# NvideaJetsonUSB.net
KiCad netlist of a schematic drawn in Altium Designer
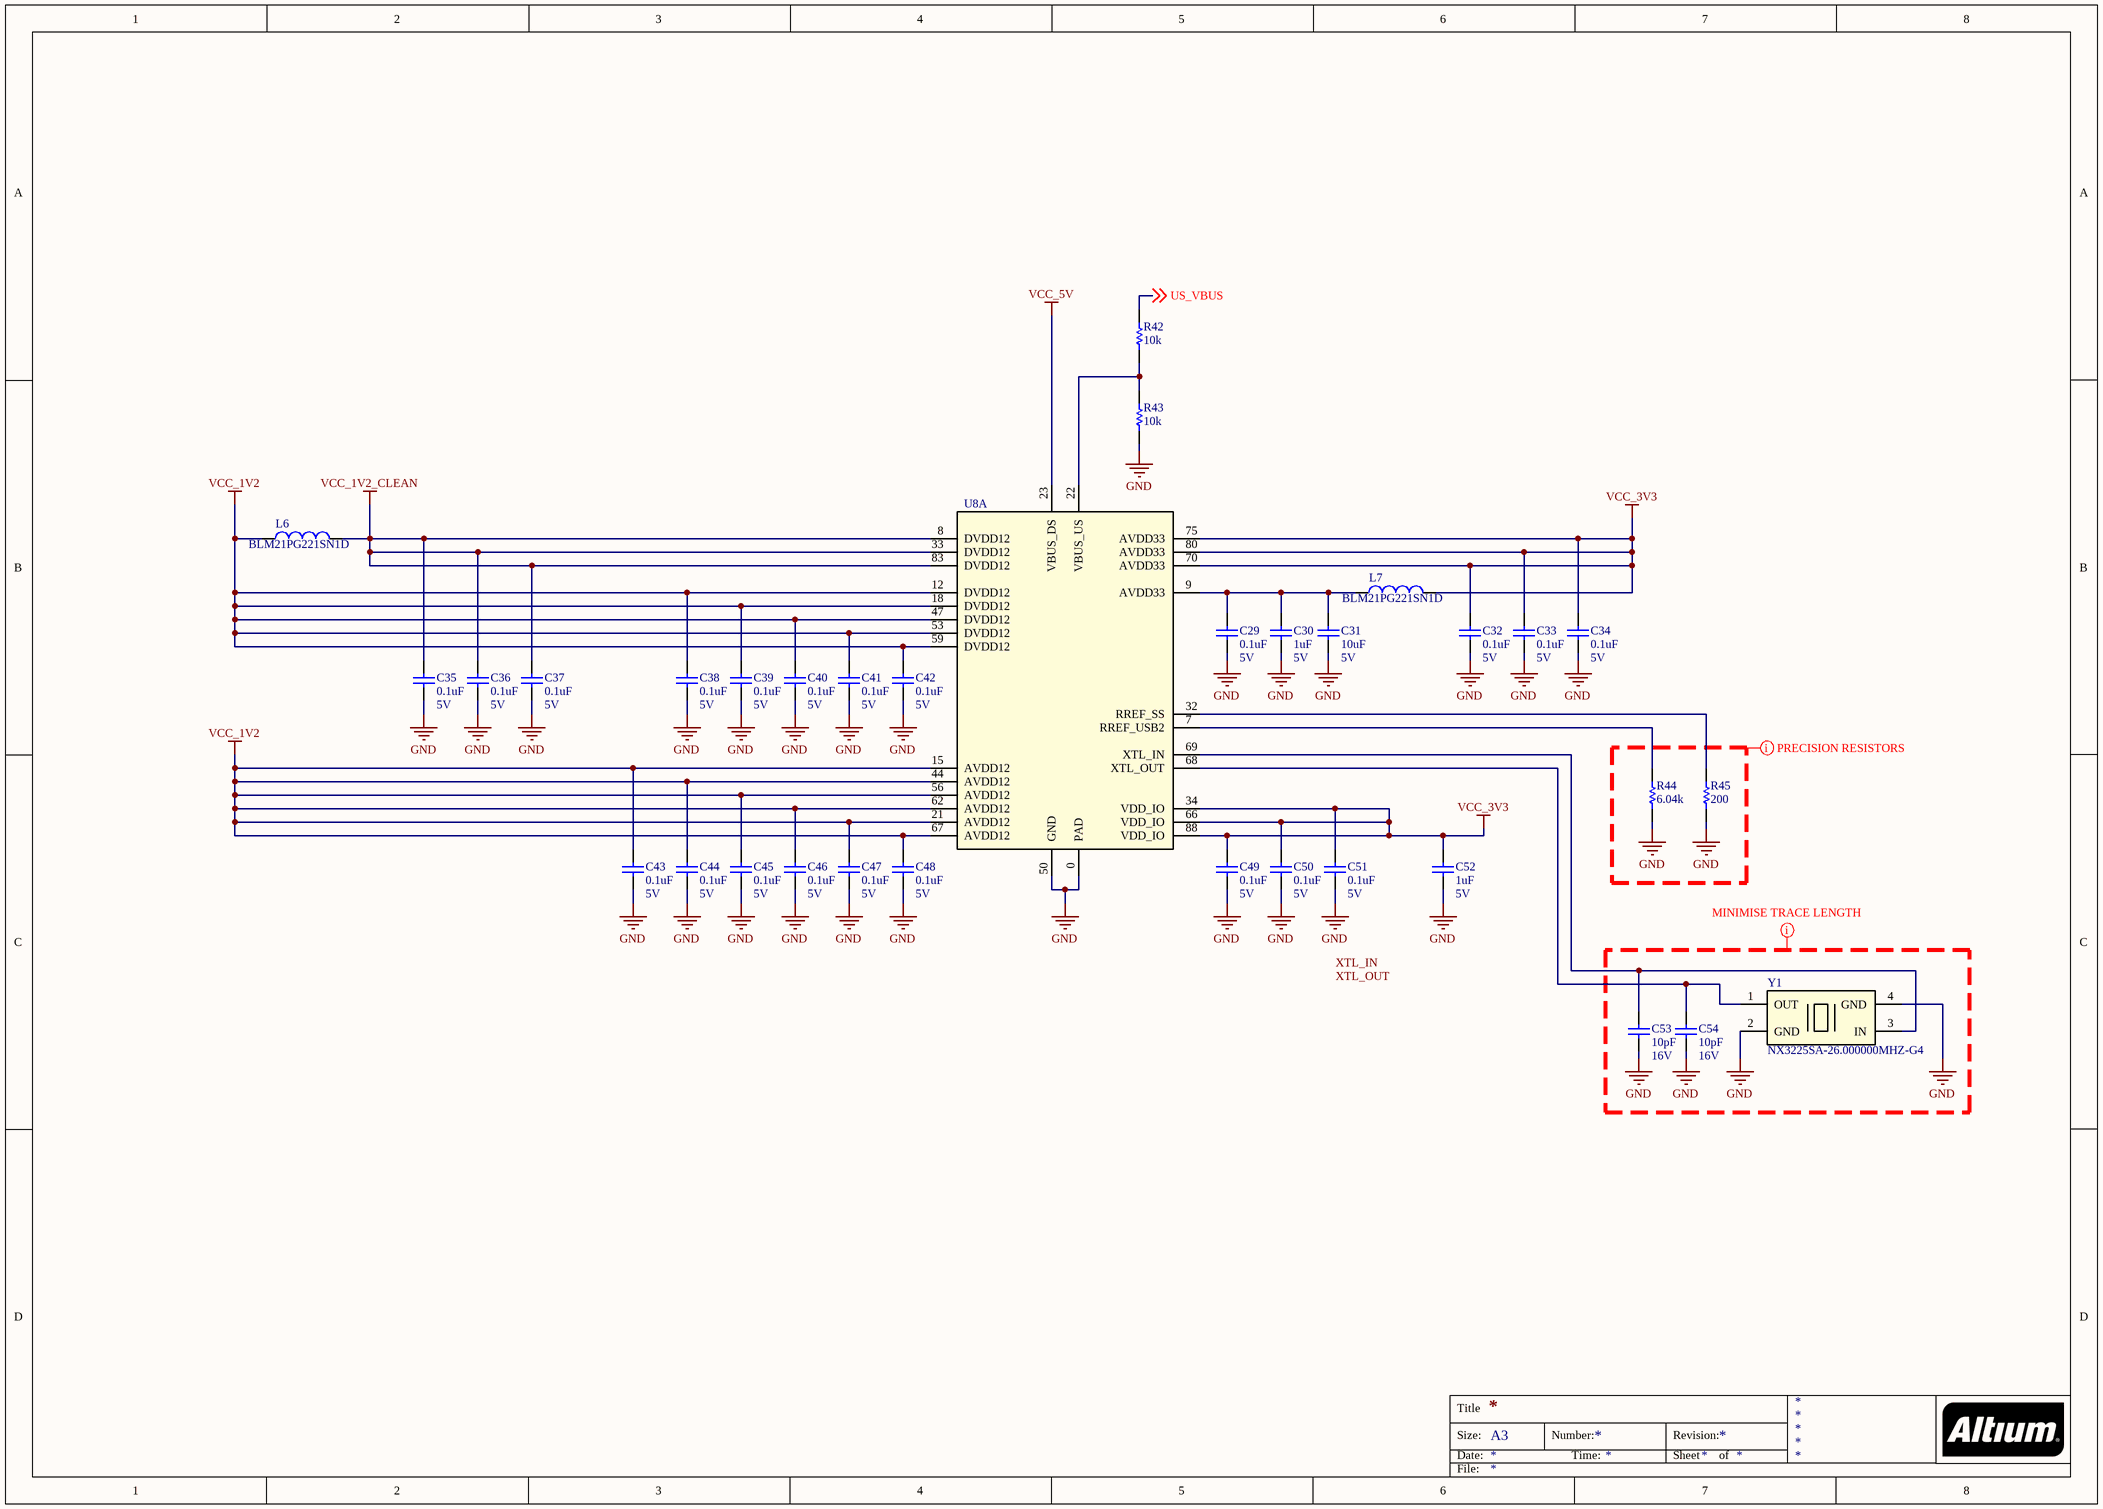
[diagram p0: NvideaJetsonUSB.SchDoc]

(export (version "E")
  (design (tool "Eeschema 10.0.6"))
  (components
    (comp (ref "C29")
      (value "0.1uF")
      (footprint "C0402")
      (description "=Description")
      (fields (field (name "VOLTAGE") "5V") (field (name "Comment") "CAP"))
      (libsource (lib "DRClib") (part "CAP"))
    )
    (comp (ref "C30")
      (value "1uF")
      (footprint "C0402")
      (description "=Description")
      (fields (field (name "VOLTAGE") "5V") (field (name "Comment") "CAP"))
      (libsource (lib "DRClib") (part "CAP"))
    )
    (comp (ref "C31")
      (value "10uF")
      (footprint "C0603")
      (description "=Description")
      (fields (field (name "VOLTAGE") "5V") (field (name "Comment") "CAP"))
      (libsource (lib "DRClib") (part "CAP"))
    )
    (comp (ref "C32")
      (value "0.1uF")
      (footprint "C0402")
      (description "=Description")
      (fields (field (name "VOLTAGE") "5V") (field (name "Comment") "CAP"))
      (libsource (lib "DRClib") (part "CAP"))
    )
    (comp (ref "C33")
      (value "0.1uF")
      (footprint "C0402")
      (description "=Description")
      (fields (field (name "VOLTAGE") "5V") (field (name "Comment") "CAP"))
      (libsource (lib "DRClib") (part "CAP"))
    )
    (comp (ref "C34")
      (value "0.1uF")
      (footprint "C0402")
      (description "=Description")
      (fields (field (name "VOLTAGE") "5V") (field (name "Comment") "CAP"))
      (libsource (lib "DRClib") (part "CAP"))
    )
    (comp (ref "C35")
      (value "0.1uF")
      (footprint "C0402")
      (description "=Description")
      (fields (field (name "VOLTAGE") "5V") (field (name "Comment") "CAP"))
      (libsource (lib "DRClib") (part "CAP"))
    )
    (comp (ref "C36")
      (value "0.1uF")
      (footprint "C0402")
      (description "=Description")
      (fields (field (name "VOLTAGE") "5V") (field (name "Comment") "CAP"))
      (libsource (lib "DRClib") (part "CAP"))
    )
    (comp (ref "C37")
      (value "0.1uF")
      (footprint "C0402")
      (description "=Description")
      (fields (field (name "VOLTAGE") "5V") (field (name "Comment") "CAP"))
      (libsource (lib "DRClib") (part "CAP"))
    )
    (comp (ref "C38")
      (value "0.1uF")
      (footprint "C0402")
      (description "=Description")
      (fields (field (name "VOLTAGE") "5V") (field (name "Comment") "CAP"))
      (libsource (lib "DRClib") (part "CAP"))
    )
    (comp (ref "C39")
      (value "0.1uF")
      (footprint "C0402")
      (description "=Description")
      (fields (field (name "VOLTAGE") "5V") (field (name "Comment") "CAP"))
      (libsource (lib "DRClib") (part "CAP"))
    )
    (comp (ref "C40")
      (value "0.1uF")
      (footprint "C0402")
      (description "=Description")
      (fields (field (name "VOLTAGE") "5V") (field (name "Comment") "CAP"))
      (libsource (lib "DRClib") (part "CAP"))
    )
    (comp (ref "C41")
      (value "0.1uF")
      (footprint "C0402")
      (description "=Description")
      (fields (field (name "VOLTAGE") "5V") (field (name "Comment") "CAP"))
      (libsource (lib "DRClib") (part "CAP"))
    )
    (comp (ref "C42")
      (value "0.1uF")
      (footprint "C0402")
      (description "=Description")
      (fields (field (name "VOLTAGE") "5V") (field (name "Comment") "CAP"))
      (libsource (lib "DRClib") (part "CAP"))
    )
    (comp (ref "C43")
      (value "0.1uF")
      (footprint "C0402")
      (description "=Description")
      (fields (field (name "VOLTAGE") "5V") (field (name "Comment") "CAP"))
      (libsource (lib "DRClib") (part "CAP"))
    )
    (comp (ref "C44")
      (value "0.1uF")
      (footprint "C0402")
      (description "=Description")
      (fields (field (name "VOLTAGE") "5V") (field (name "Comment") "CAP"))
      (libsource (lib "DRClib") (part "CAP"))
    )
    (comp (ref "C45")
      (value "0.1uF")
      (footprint "C0402")
      (description "=Description")
      (fields (field (name "VOLTAGE") "5V") (field (name "Comment") "CAP"))
      (libsource (lib "DRClib") (part "CAP"))
    )
    (comp (ref "C46")
      (value "0.1uF")
      (footprint "C0402")
      (description "=Description")
      (fields (field (name "VOLTAGE") "5V") (field (name "Comment") "CAP"))
      (libsource (lib "DRClib") (part "CAP"))
    )
    (comp (ref "C47")
      (value "0.1uF")
      (footprint "C0402")
      (description "=Description")
      (fields (field (name "VOLTAGE") "5V") (field (name "Comment") "CAP"))
      (libsource (lib "DRClib") (part "CAP"))
    )
    (comp (ref "C48")
      (value "0.1uF")
      (footprint "C0402")
      (description "=Description")
      (fields (field (name "VOLTAGE") "5V") (field (name "Comment") "CAP"))
      (libsource (lib "DRClib") (part "CAP"))
    )
    (comp (ref "C49")
      (value "0.1uF")
      (footprint "C0402")
      (description "=Description")
      (fields (field (name "VOLTAGE") "5V") (field (name "Comment") "CAP"))
      (libsource (lib "DRClib") (part "CAP"))
    )
    (comp (ref "C50")
      (value "0.1uF")
      (footprint "C0402")
      (description "=Description")
      (fields (field (name "VOLTAGE") "5V") (field (name "Comment") "CAP"))
      (libsource (lib "DRClib") (part "CAP"))
    )
    (comp (ref "C51")
      (value "0.1uF")
      (footprint "C0402")
      (description "=Description")
      (fields (field (name "VOLTAGE") "5V") (field (name "Comment") "CAP"))
      (libsource (lib "DRClib") (part "CAP"))
    )
    (comp (ref "C52")
      (value "1uF")
      (footprint "C0402")
      (description "=Description")
      (fields (field (name "VOLTAGE") "5V") (field (name "Comment") "CAP"))
      (libsource (lib "DRClib") (part "CAP"))
    )
    (comp (ref "C53")
      (value "10pF")
      (footprint "C0402")
      (description "=Description")
      (fields (field (name "VOLTAGE") "16V") (field (name "Comment") "CAP"))
      (libsource (lib "DRClib") (part "CAP"))
    )
    (comp (ref "C54")
      (value "10pF")
      (footprint "C0402")
      (description "=Description")
      (fields (field (name "VOLTAGE") "16V") (field (name "Comment") "CAP"))
      (libsource (lib "DRClib") (part "CAP"))
    )
    (comp (ref "L6")
      (value "BLM21PG221SN1D")
      (footprint "L0603")
      (description "BLM21PG221SN1D Ferrite Bead")
      (fields (field (name "Comment") "IND"))
      (libsource (lib "DRClib") (part "IND"))
    )
    (comp (ref "L7")
      (value "BLM21PG221SN1D")
      (footprint "L0603")
      (description "BLM21PG221SN1D Ferrite Bead")
      (fields (field (name "Comment") "IND"))
      (libsource (lib "DRClib") (part "IND"))
    )
    (comp (ref "R42")
      (value "10k")
      (footprint "R0402")
      (description "=Description")
      (fields (field (name "Comment") "RES"))
      (libsource (lib "DRClib") (part "RES"))
    )
    (comp (ref "R43")
      (value "10k")
      (footprint "R0402")
      (description "=Description")
      (fields (field (name "Comment") "RES"))
      (libsource (lib "DRClib") (part "RES"))
    )
    (comp (ref "R44")
      (value "6.04k")
      (footprint "R0402")
      (description "=Description")
      (fields (field (name "Comment") "RES"))
      (libsource (lib "DRClib") (part "RES"))
    )
    (comp (ref "R45")
      (value "200")
      (footprint "R0402")
      (description "=Description")
      (fields (field (name "Comment") "RES"))
      (libsource (lib "DRClib") (part "RES"))
    )
    (comp (ref "U8")
      (value "CYUSB3312-88LTXC")
      (footprint "QFN88")
      (description "USB3.0 Hub")
      (fields (field (name "MP") "2309411-2") (field (name "MF") "TE Connectivity"))
      (libsource (lib "DRClib") (part "CYUSB3312-88LTXC"))
    )
    (comp (ref "Y1")
      (value "CRYSTAL")
      (footprint "NX3225SA-26.000000MHZ-G4")
      (fields (field (name "PART_NO.") "NX3225SA-26.000000MHZ-G4"))
      (libsource (lib "DRClib") (part "CRYSTAL"))
    )
  )
  (nets
    (net (code "3") (name "GND") (class "Default")
      (node (ref "C29") (pin "2") (pinfunction "2_2") (pintype "passive"))
      (node (ref "C30") (pin "2") (pinfunction "2_2") (pintype "passive"))
      (node (ref "C31") (pin "2") (pinfunction "2_2") (pintype "passive"))
      (node (ref "C32") (pin "2") (pinfunction "2_2") (pintype "passive"))
      (node (ref "C33") (pin "2") (pinfunction "2_2") (pintype "passive"))
      (node (ref "C34") (pin "2") (pinfunction "2_2") (pintype "passive"))
      (node (ref "C35") (pin "2") (pinfunction "2_2") (pintype "passive"))
      (node (ref "C36") (pin "2") (pinfunction "2_2") (pintype "passive"))
      (node (ref "C37") (pin "2") (pinfunction "2_2") (pintype "passive"))
      (node (ref "C38") (pin "2") (pinfunction "2_2") (pintype "passive"))
      (node (ref "C39") (pin "2") (pinfunction "2_2") (pintype "passive"))
      (node (ref "C40") (pin "2") (pinfunction "2_2") (pintype "passive"))
      (node (ref "C41") (pin "2") (pinfunction "2_2") (pintype "passive"))
      (node (ref "C42") (pin "2") (pinfunction "2_2") (pintype "passive"))
      (node (ref "C43") (pin "2") (pinfunction "2_2") (pintype "passive"))
      (node (ref "C44") (pin "2") (pinfunction "2_2") (pintype "passive"))
      (node (ref "C45") (pin "2") (pinfunction "2_2") (pintype "passive"))
      (node (ref "C46") (pin "2") (pinfunction "2_2") (pintype "passive"))
      (node (ref "C47") (pin "2") (pinfunction "2_2") (pintype "passive"))
      (node (ref "C48") (pin "2") (pinfunction "2_2") (pintype "passive"))
      (node (ref "C49") (pin "2") (pinfunction "2_2") (pintype "passive"))
      (node (ref "C50") (pin "2") (pinfunction "2_2") (pintype "passive"))
      (node (ref "C51") (pin "2") (pinfunction "2_2") (pintype "passive"))
      (node (ref "C52") (pin "2") (pinfunction "2_2") (pintype "passive"))
      (node (ref "C53") (pin "2") (pinfunction "2_2") (pintype "passive"))
      (node (ref "C54") (pin "2") (pinfunction "2_2") (pintype "passive"))
      (node (ref "R43") (pin "2") (pinfunction "2_2") (pintype "passive"))
      (node (ref "R44") (pin "2") (pinfunction "2_2") (pintype "passive"))
      (node (ref "R45") (pin "1") (pinfunction "1_1") (pintype "passive"))
      (node (ref "U8") (pin "0") (pinfunction "PAD_0") (pintype "passive"))
      (node (ref "U8") (pin "50") (pinfunction "GND_50") (pintype "passive"))
      (node (ref "Y1") (pin "2") (pinfunction "GND_2") (pintype "passive"))
      (node (ref "Y1") (pin "4") (pinfunction "GND_4") (pintype "passive"))
    )
    (net (code "4") (name "Net-(C29-Pad1)") (class "Default")
      (node (ref "C29") (pin "1") (pinfunction "1_1") (pintype "passive"))
      (node (ref "C30") (pin "1") (pinfunction "1_1") (pintype "passive"))
      (node (ref "C31") (pin "1") (pinfunction "1_1") (pintype "passive"))
      (node (ref "L7") (pin "1") (pinfunction "1_1") (pintype "passive"))
      (node (ref "U8") (pin "9") (pinfunction "AVDD33_9") (pintype "passive"))
    )
    (net (code "5") (name "Net-(U8A-RREF_SS)") (class "Default")
      (node (ref "R45") (pin "2") (pinfunction "2_2") (pintype "passive"))
      (node (ref "U8") (pin "32") (pinfunction "RREF_SS_32") (pintype "passive"))
    )
    (net (code "6") (name "Net-(U8A-RREF_USB2)") (class "Default")
      (node (ref "R44") (pin "1") (pinfunction "1_1") (pintype "passive"))
      (node (ref "U8") (pin "7") (pinfunction "RREF_USB2_7") (pintype "passive"))
    )
    (net (code "7") (name "Net-(U8A-VBUS_US)") (class "Default")
      (node (ref "R42") (pin "2") (pinfunction "2_2") (pintype "passive"))
      (node (ref "R43") (pin "1") (pinfunction "1_1") (pintype "passive"))
      (node (ref "U8") (pin "22") (pinfunction "VBUS_US_22") (pintype "passive"))
    )
    (net (code "8") (name "Net-(U8A-XTL_IN)") (class "Default")
      (node (ref "C53") (pin "1") (pinfunction "1_1") (pintype "passive"))
      (node (ref "U8") (pin "69") (pinfunction "XTL_IN_69") (pintype "passive"))
      (node (ref "Y1") (pin "3") (pinfunction "IN_3") (pintype "passive"))
    )
    (net (code "9") (name "Net-(U8A-XTL_OUT)") (class "Default")
      (node (ref "C54") (pin "1") (pinfunction "1_1") (pintype "passive"))
      (node (ref "U8") (pin "68") (pinfunction "XTL_OUT_68") (pintype "passive"))
      (node (ref "Y1") (pin "1") (pinfunction "OUT_1") (pintype "passive"))
    )
    (net (code "10") (name "US_VBUS") (class "Default")
      (node (ref "R42") (pin "1") (pinfunction "1_1") (pintype "passive"))
    )
    (net (code "11") (name "VCC_1V2") (class "Default")
      (node (ref "C38") (pin "1") (pinfunction "1_1") (pintype "passive"))
      (node (ref "C39") (pin "1") (pinfunction "1_1") (pintype "passive"))
      (node (ref "C40") (pin "1") (pinfunction "1_1") (pintype "passive"))
      (node (ref "C41") (pin "1") (pinfunction "1_1") (pintype "passive"))
      (node (ref "C42") (pin "1") (pinfunction "1_1") (pintype "passive"))
      (node (ref "C43") (pin "1") (pinfunction "1_1") (pintype "passive"))
      (node (ref "C44") (pin "1") (pinfunction "1_1") (pintype "passive"))
      (node (ref "C45") (pin "1") (pinfunction "1_1") (pintype "passive"))
      (node (ref "C46") (pin "1") (pinfunction "1_1") (pintype "passive"))
      (node (ref "C47") (pin "1") (pinfunction "1_1") (pintype "passive"))
      (node (ref "C48") (pin "1") (pinfunction "1_1") (pintype "passive"))
      (node (ref "L6") (pin "1") (pinfunction "1_1") (pintype "passive"))
      (node (ref "U8") (pin "12") (pinfunction "DVDD12_12") (pintype "passive"))
      (node (ref "U8") (pin "15") (pinfunction "AVDD12_15") (pintype "passive"))
      (node (ref "U8") (pin "18") (pinfunction "DVDD12_18") (pintype "passive"))
      (node (ref "U8") (pin "21") (pinfunction "AVDD12_21") (pintype "passive"))
      (node (ref "U8") (pin "44") (pinfunction "AVDD12_44") (pintype "passive"))
      (node (ref "U8") (pin "47") (pinfunction "DVDD12_47") (pintype "passive"))
      (node (ref "U8") (pin "53") (pinfunction "DVDD12_53") (pintype "passive"))
      (node (ref "U8") (pin "56") (pinfunction "AVDD12_56") (pintype "passive"))
      (node (ref "U8") (pin "59") (pinfunction "DVDD12_59") (pintype "passive"))
      (node (ref "U8") (pin "62") (pinfunction "AVDD12_62") (pintype "passive"))
      (node (ref "U8") (pin "67") (pinfunction "AVDD12_67") (pintype "passive"))
    )
    (net (code "12") (name "VCC_1V2_CLEAN") (class "Default")
      (node (ref "C35") (pin "1") (pinfunction "1_1") (pintype "passive"))
      (node (ref "C36") (pin "1") (pinfunction "1_1") (pintype "passive"))
      (node (ref "C37") (pin "1") (pinfunction "1_1") (pintype "passive"))
      (node (ref "L6") (pin "2") (pinfunction "2_2") (pintype "passive"))
      (node (ref "U8") (pin "33") (pinfunction "DVDD12_33") (pintype "passive"))
      (node (ref "U8") (pin "8") (pinfunction "DVDD12_8") (pintype "passive"))
      (node (ref "U8") (pin "83") (pinfunction "DVDD12_83") (pintype "passive"))
    )
    (net (code "13") (name "VCC_3V3") (class "Default")
      (node (ref "C32") (pin "1") (pinfunction "1_1") (pintype "passive"))
      (node (ref "C33") (pin "1") (pinfunction "1_1") (pintype "passive"))
      (node (ref "C34") (pin "1") (pinfunction "1_1") (pintype "passive"))
      (node (ref "C49") (pin "1") (pinfunction "1_1") (pintype "passive"))
      (node (ref "C50") (pin "1") (pinfunction "1_1") (pintype "passive"))
      (node (ref "C51") (pin "1") (pinfunction "1_1") (pintype "passive"))
      (node (ref "C52") (pin "1") (pinfunction "1_1") (pintype "passive"))
      (node (ref "L7") (pin "2") (pinfunction "2_2") (pintype "passive"))
      (node (ref "U8") (pin "34") (pinfunction "VDD_IO_34") (pintype "passive"))
      (node (ref "U8") (pin "66") (pinfunction "VDD_IO_66") (pintype "passive"))
      (node (ref "U8") (pin "70") (pinfunction "AVDD33_70") (pintype "passive"))
      (node (ref "U8") (pin "75") (pinfunction "AVDD33_75") (pintype "passive"))
      (node (ref "U8") (pin "80") (pinfunction "AVDD33_80") (pintype "passive"))
      (node (ref "U8") (pin "88") (pinfunction "VDD_IO_88") (pintype "passive"))
    )
    (net (code "14") (name "VCC_5V") (class "Default")
      (node (ref "U8") (pin "23") (pinfunction "VBUS_DS_23") (pintype "passive"))
    )
  )
)
